# Sheet2.net
KiCad netlist of a schematic drawn in Altium Designer
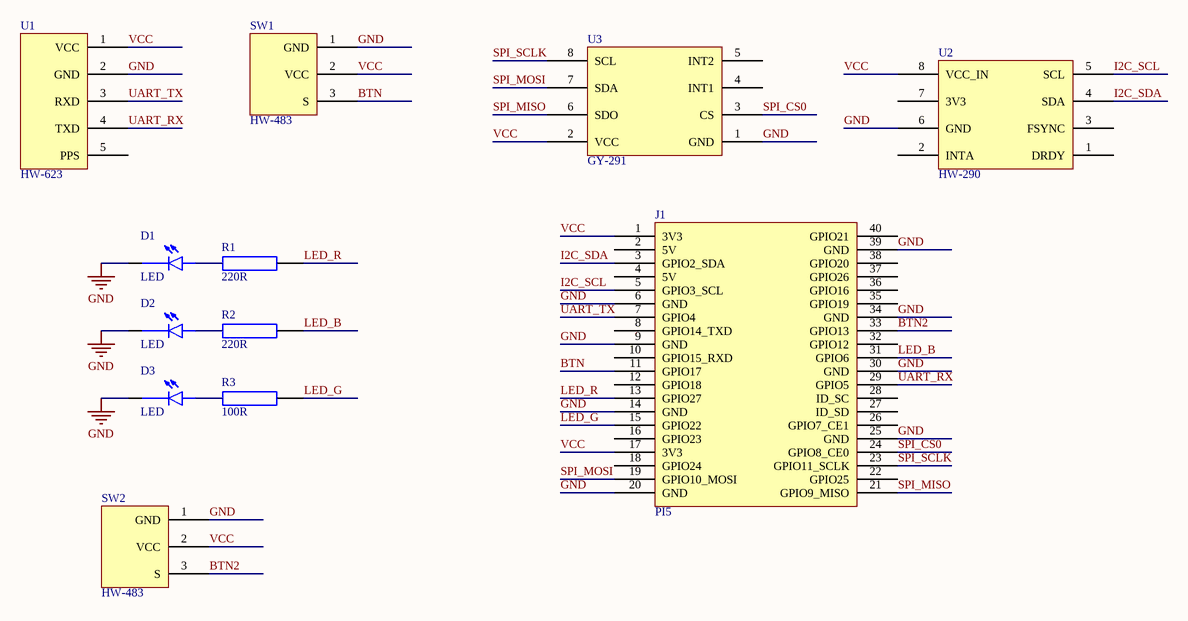
[diagram p0: Sheet2.SchDoc]

(export (version "E")
  (design (tool "Eeschema 10.0.6"))
  (components
    (comp (ref "D1") (value "LED") (footprint "LED") (libsource (lib "Schlib2") (part "LED")))
    (comp (ref "D2") (value "LED") (footprint "LED") (libsource (lib "Schlib2") (part "LED")))
    (comp (ref "D3") (value "LED") (footprint "LED") (libsource (lib "Schlib2") (part "LED")))
    (comp (ref "J1") (value "PI5") (footprint "PI5") (libsource (lib "Schlib2") (part "PI5")))
    (comp (ref "R1") (value "220R") (footprint "Resistor") (libsource (lib "Schlib2") (part "Resistor")))
    (comp (ref "R2") (value "220R") (footprint "Resistor") (libsource (lib "Schlib2") (part "Resistor")))
    (comp (ref "R3") (value "100R") (footprint "Resistor") (libsource (lib "Schlib2") (part "Resistor")))
    (comp (ref "SW1") (value "HW-483") (footprint "HW-483") (libsource (lib "Schlib2") (part "HW-483")))
    (comp (ref "SW2") (value "HW-483") (footprint "HW-483") (libsource (lib "Schlib2") (part "HW-483")))
    (comp (ref "U1") (value "HW-623") (footprint "HW-623") (libsource (lib "Schlib2") (part "HW-623")))
    (comp (ref "U2") (value "HW-290") (footprint "HW-290") (libsource (lib "Schlib2") (part "HW290_GY87")))
    (comp (ref "U3") (value "GY-291") (footprint "GY-291") (libsource (lib "Schlib2") (part "GY-291")))
  )
  (nets
    (net (code "2") (name "/BTN") (class "Default")
      (node (ref "J1") (pin "11") (pinfunction "GPIO17_11") (pintype "passive"))
      (node (ref "SW1") (pin "3") (pinfunction "S_3") (pintype "passive"))
    )
    (net (code "3") (name "/BTN2") (class "Default")
      (node (ref "J1") (pin "33") (pinfunction "GPIO13_33") (pintype "passive"))
      (node (ref "SW2") (pin "3") (pinfunction "S_3") (pintype "passive"))
    )
    (net (code "4") (name "/I2C_SCL") (class "Default")
      (node (ref "J1") (pin "5") (pinfunction "GPIO3_SCL_5") (pintype "passive"))
      (node (ref "U2") (pin "5") (pinfunction "SCL_5") (pintype "passive"))
    )
    (net (code "5") (name "/I2C_SDA") (class "Default")
      (node (ref "J1") (pin "3") (pinfunction "GPIO2_SDA_3") (pintype "passive"))
      (node (ref "U2") (pin "4") (pinfunction "SDA_4") (pintype "passive"))
    )
    (net (code "6") (name "/LED_B") (class "Default")
      (node (ref "J1") (pin "31") (pinfunction "GPIO6_31") (pintype "passive"))
      (node (ref "R2") (pin "2") (pinfunction "2_2") (pintype "passive"))
    )
    (net (code "7") (name "/LED_G") (class "Default")
      (node (ref "J1") (pin "15") (pinfunction "GPIO22_15") (pintype "passive"))
      (node (ref "R3") (pin "2") (pinfunction "2_2") (pintype "passive"))
    )
    (net (code "8") (name "/LED_R") (class "Default")
      (node (ref "J1") (pin "13") (pinfunction "GPIO27_13") (pintype "passive"))
      (node (ref "R1") (pin "2") (pinfunction "2_2") (pintype "passive"))
    )
    (net (code "9") (name "/SPI_CS0") (class "Default")
      (node (ref "J1") (pin "24") (pinfunction "GPIO8_CE0_24") (pintype "passive"))
      (node (ref "U3") (pin "3") (pinfunction "CS_3") (pintype "passive"))
    )
    (net (code "10") (name "/SPI_MISO") (class "Default")
      (node (ref "J1") (pin "21") (pinfunction "GPIO9_MISO_21") (pintype "passive"))
      (node (ref "U3") (pin "6") (pinfunction "SDO_6") (pintype "passive"))
    )
    (net (code "11") (name "/SPI_MOSI") (class "Default")
      (node (ref "J1") (pin "19") (pinfunction "GPIO10_MOSI_19") (pintype "passive"))
      (node (ref "U3") (pin "7") (pinfunction "SDA_7") (pintype "passive"))
    )
    (net (code "12") (name "/SPI_SCLK") (class "Default")
      (node (ref "J1") (pin "23") (pinfunction "GPIO11_SCLK_23") (pintype "passive"))
      (node (ref "U3") (pin "8") (pinfunction "SCL_8") (pintype "passive"))
    )
    (net (code "13") (name "/UART_RX") (class "Default")
      (node (ref "J1") (pin "29") (pinfunction "GPIO5_29") (pintype "passive"))
      (node (ref "U1") (pin "4") (pinfunction "TXD_4") (pintype "passive"))
    )
    (net (code "14") (name "/UART_TX") (class "Default")
      (node (ref "J1") (pin "7") (pinfunction "GPIO4_7") (pintype "passive"))
      (node (ref "U1") (pin "3") (pinfunction "RXD_3") (pintype "passive"))
    )
    (net (code "15") (name "/VCC") (class "Default")
      (node (ref "J1") (pin "1") (pinfunction "3V3_1") (pintype "passive"))
      (node (ref "J1") (pin "17") (pinfunction "3V3_17") (pintype "passive"))
      (node (ref "SW1") (pin "2") (pinfunction "VCC_2") (pintype "passive"))
      (node (ref "SW2") (pin "2") (pinfunction "VCC_2") (pintype "passive"))
      (node (ref "U1") (pin "1") (pinfunction "VCC_1") (pintype "passive"))
      (node (ref "U2") (pin "8") (pinfunction "VCC_IN_8") (pintype "passive"))
      (node (ref "U3") (pin "2") (pinfunction "VCC_2") (pintype "passive"))
    )
    (net (code "16") (name "GND") (class "Default")
      (node (ref "D1") (pin "C") (pinfunction "C_C") (pintype "passive"))
      (node (ref "D2") (pin "C") (pinfunction "C_C") (pintype "passive"))
      (node (ref "D3") (pin "C") (pinfunction "C_C") (pintype "passive"))
      (node (ref "J1") (pin "14") (pinfunction "GND_14") (pintype "passive"))
      (node (ref "J1") (pin "20") (pinfunction "GND_20") (pintype "passive"))
      (node (ref "J1") (pin "25") (pinfunction "GND_25") (pintype "passive"))
      (node (ref "J1") (pin "30") (pinfunction "GND_30") (pintype "passive"))
      (node (ref "J1") (pin "34") (pinfunction "GND_34") (pintype "passive"))
      (node (ref "J1") (pin "39") (pinfunction "GND_39") (pintype "passive"))
      (node (ref "J1") (pin "6") (pinfunction "GND_6") (pintype "passive"))
      (node (ref "J1") (pin "9") (pinfunction "GND_9") (pintype "passive"))
      (node (ref "SW1") (pin "1") (pinfunction "GND_1") (pintype "passive"))
      (node (ref "SW2") (pin "1") (pinfunction "GND_1") (pintype "passive"))
      (node (ref "U1") (pin "2") (pinfunction "GND_2") (pintype "passive"))
      (node (ref "U2") (pin "6") (pinfunction "GND_6") (pintype "passive"))
      (node (ref "U3") (pin "1") (pinfunction "GND_1") (pintype "passive"))
    )
    (net (code "17") (name "Net-(D1-PadA)") (class "Default")
      (node (ref "D1") (pin "A") (pinfunction "A_A") (pintype "passive"))
      (node (ref "R1") (pin "1") (pinfunction "1_1") (pintype "passive"))
    )
    (net (code "18") (name "Net-(D2-PadA)") (class "Default")
      (node (ref "D2") (pin "A") (pinfunction "A_A") (pintype "passive"))
      (node (ref "R2") (pin "1") (pinfunction "1_1") (pintype "passive"))
    )
    (net (code "19") (name "Net-(D3-PadA)") (class "Default")
      (node (ref "D3") (pin "A") (pinfunction "A_A") (pintype "passive"))
      (node (ref "R3") (pin "1") (pinfunction "1_1") (pintype "passive"))
    )
    (net (code "20") (name "unconnected-(J1-5V-Pad2)") (class "Default")
      (node (ref "J1") (pin "2") (pinfunction "5V_2") (pintype "passive"))
    )
    (net (code "21") (name "unconnected-(J1-5V-Pad4)") (class "Default")
      (node (ref "J1") (pin "4") (pinfunction "5V_4") (pintype "passive"))
    )
    (net (code "22") (name "unconnected-(J1-GPIO7_CE1-Pad26)") (class "Default")
      (node (ref "J1") (pin "26") (pinfunction "GPIO7_CE1_26") (pintype "passive"))
    )
    (net (code "23") (name "unconnected-(J1-GPIO12-Pad32)") (class "Default")
      (node (ref "J1") (pin "32") (pinfunction "GPIO12_32") (pintype "passive"))
    )
    (net (code "24") (name "unconnected-(J1-GPIO14_TXD-Pad8)") (class "Default")
      (node (ref "J1") (pin "8") (pinfunction "GPIO14_TXD_8") (pintype "passive"))
    )
    (net (code "25") (name "unconnected-(J1-GPIO15_RXD-Pad10)") (class "Default")
      (node (ref "J1") (pin "10") (pinfunction "GPIO15_RXD_10") (pintype "passive"))
    )
    (net (code "26") (name "unconnected-(J1-GPIO16-Pad36)") (class "Default")
      (node (ref "J1") (pin "36") (pinfunction "GPIO16_36") (pintype "passive"))
    )
    (net (code "27") (name "unconnected-(J1-GPIO18-Pad12)") (class "Default")
      (node (ref "J1") (pin "12") (pinfunction "GPIO18_12") (pintype "passive"))
    )
    (net (code "28") (name "unconnected-(J1-GPIO19-Pad35)") (class "Default")
      (node (ref "J1") (pin "35") (pinfunction "GPIO19_35") (pintype "passive"))
    )
    (net (code "29") (name "unconnected-(J1-GPIO20-Pad38)") (class "Default")
      (node (ref "J1") (pin "38") (pinfunction "GPIO20_38") (pintype "passive"))
    )
    (net (code "30") (name "unconnected-(J1-GPIO21-Pad40)") (class "Default")
      (node (ref "J1") (pin "40") (pinfunction "GPIO21_40") (pintype "passive"))
    )
    (net (code "31") (name "unconnected-(J1-GPIO23-Pad16)") (class "Default")
      (node (ref "J1") (pin "16") (pinfunction "GPIO23_16") (pintype "passive"))
    )
    (net (code "32") (name "unconnected-(J1-GPIO24-Pad18)") (class "Default")
      (node (ref "J1") (pin "18") (pinfunction "GPIO24_18") (pintype "passive"))
    )
    (net (code "33") (name "unconnected-(J1-GPIO25-Pad22)") (class "Default")
      (node (ref "J1") (pin "22") (pinfunction "GPIO25_22") (pintype "passive"))
    )
    (net (code "34") (name "unconnected-(J1-GPIO26-Pad37)") (class "Default")
      (node (ref "J1") (pin "37") (pinfunction "GPIO26_37") (pintype "passive"))
    )
    (net (code "35") (name "unconnected-(J1-ID_SC-Pad28)") (class "Default")
      (node (ref "J1") (pin "28") (pinfunction "ID_SC_28") (pintype "passive"))
    )
    (net (code "36") (name "unconnected-(J1-ID_SD-Pad27)") (class "Default")
      (node (ref "J1") (pin "27") (pinfunction "ID_SD_27") (pintype "passive"))
    )
    (net (code "37") (name "unconnected-(U1-PPS-Pad5)") (class "Default")
      (node (ref "U1") (pin "5") (pinfunction "PPS_5") (pintype "passive"))
    )
    (net (code "38") (name "unconnected-(U2-3V3-Pad7)") (class "Default")
      (node (ref "U2") (pin "7") (pinfunction "3V3_7") (pintype "passive"))
    )
    (net (code "39") (name "unconnected-(U2-DRDY-Pad1)") (class "Default")
      (node (ref "U2") (pin "1") (pinfunction "DRDY_1") (pintype "passive"))
    )
    (net (code "40") (name "unconnected-(U2-FSYNC-Pad3)") (class "Default")
      (node (ref "U2") (pin "3") (pinfunction "FSYNC_3") (pintype "passive"))
    )
    (net (code "41") (name "unconnected-(U2-INTA-Pad2)") (class "Default")
      (node (ref "U2") (pin "2") (pinfunction "INTA_2") (pintype "passive"))
    )
    (net (code "42") (name "unconnected-(U3-INT1-Pad4)") (class "Default")
      (node (ref "U3") (pin "4") (pinfunction "INT1_4") (pintype "passive"))
    )
    (net (code "43") (name "unconnected-(U3-INT2-Pad5)") (class "Default")
      (node (ref "U3") (pin "5") (pinfunction "INT2_5") (pintype "passive"))
    )
  )
)
